# LTR-329ALS-01_StemmaQT.net
KiCad netlist of a schematic drawn in Altium Designer
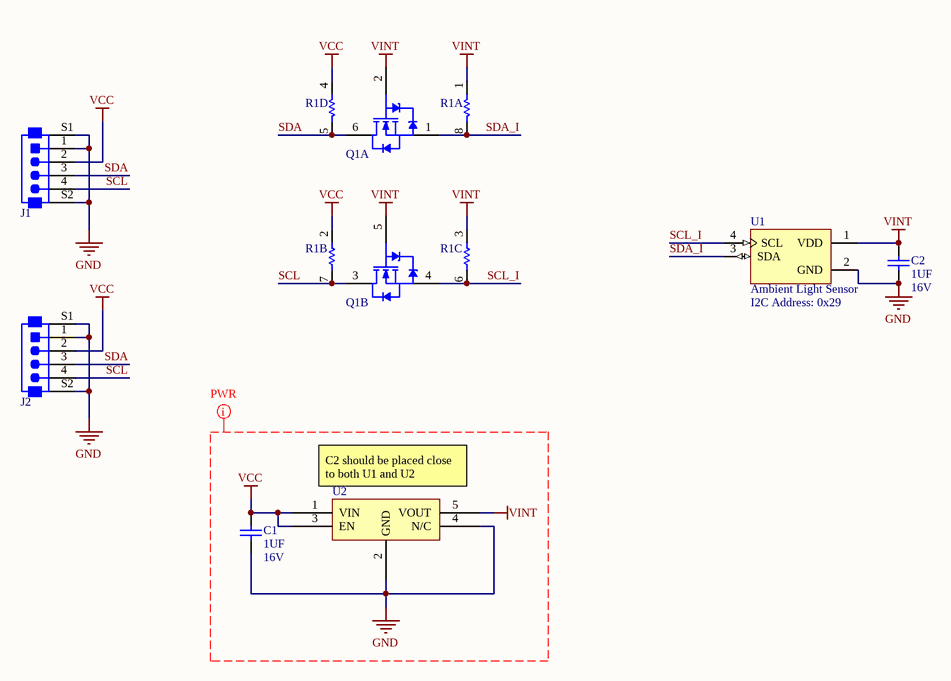
[diagram p0: LTR-329ALS-01 StemmaQT.SchDoc]

(export (version "E")
  (design (tool "Eeschema 10.0.6"))
  (components
    (comp (ref "C1")
      (value "CAP 0603 1UF 16V 10% X7R")
      (footprint "0603_CAP")
      (description "Capacitor Surface Mount 0603 Footprint 1UF 16V 10% Tolerance Ceramic X7R")
      (fields
        (field (name "VAL") "1UF")
        (field (name "VOL") "16V")
        (field (name "MANUFACTURER") "Various")
        (field (name "VOLTAGE") "16V")
      )
      (libsource (lib "Passive Components") (part "cap"))
    )
    (comp (ref "C2")
      (value "CAP 0603 1UF 16V 10% X7R")
      (footprint "0603_CAP")
      (description "Capacitor Surface Mount 0603 Footprint 1UF 16V 10% Tolerance Ceramic X7R")
      (fields
        (field (name "VAL") "1UF")
        (field (name "VOL") "16V")
        (field (name "MANUFACTURER") "Various")
        (field (name "VOLTAGE") "16V")
      )
      (libsource (lib "Passive Components") (part "cap"))
    )
    (comp (ref "J1")
      (value "4 Pin, 1mm")
      (footprint "SM04B-SRSS-TB")
      (description "JST 4-Pin SR Series, SMD (1MM, 4 Pos)")
      (fields (field (name "MANUFACTURER") "J.S.T. Mfg. Co.,Ltd"))
      (libsource (lib "Connectors") (part "Header 1X4 2 SHIELD SIDE"))
    )
    (comp (ref "J2")
      (value "4 Pin, 1mm")
      (footprint "SM04B-SRSS-TB")
      (description "JST 4-Pin SR Series, SMD (1MM, 4 Pos)")
      (fields (field (name "MANUFACTURER") "J.S.T. Mfg. Co.,Ltd"))
      (libsource (lib "Connectors") (part "Header 1X4 2 SHIELD SIDE"))
    )
    (comp (ref "Q1")
      (value "Dual N-Channel MOSFET")
      (footprint "SOT363")
      (description "Dual N-Channel Trench MOSFET, 60 V, 0.32 A SOT-363")
      (fields (field (name "MANUFACTURER") "NXP Semiconductors"))
      (libsource (lib "Discrete Semiconductors") (part "BSS138BKS"))
    )
    (comp (ref "R1")
      (value "10k ohm resistor array")
      (footprint "CAY16-J4")
      (fields (field (name "MANUFACTURER") "Bourns Inc."))
      (libsource (lib "Passive Components") (part "res_pack_4"))
    )
    (comp (ref "U1")
      (value "Ambient Light Sensor")
      (footprint "LTR-329ALS-01-MFG")
      (description "Optical Sensor Ambient  I²C 4-VDFN")
      (fields (field (name "I2C ADDRESS") "0x29") (field (name "MANUFACTURER") "Lite-On Inc."))
      (libsource (lib "Sensors") (part "LTR-329ALS-01"))
    )
    (comp (ref "U2")
      (value "2.5V LDO")
      (footprint "SOT23-5")
      (description "Linear Voltage Regulator IC  1 Output  250mA SOT-23-5")
      (fields (field (name "MANUFACTURER") "Texas Insturments"))
      (libsource (lib "Integrated Circuits") (part "LP5907MFX"))
    )
  )
  (nets
    (net (code "1") (name "/SCL") (class "Default")
      (node (ref "J1") (pin "4") (pinfunction "4_4") (pintype "passive"))
      (node (ref "J2") (pin "4") (pinfunction "4_4") (pintype "passive"))
      (node (ref "Q1") (pin "3") (pinfunction "D2_3") (pintype "passive"))
      (node (ref "R1") (pin "7") (pinfunction "7_7") (pintype "passive"))
    )
    (net (code "2") (name "/SCL_I") (class "Default")
      (node (ref "Q1") (pin "4") (pinfunction "S2_4") (pintype "passive"))
      (node (ref "R1") (pin "6") (pinfunction "6_6") (pintype "passive"))
      (node (ref "U1") (pin "4") (pinfunction "SCL_4") (pintype "input"))
    )
    (net (code "3") (name "/SDA") (class "Default")
      (node (ref "J1") (pin "3") (pinfunction "3_3") (pintype "passive"))
      (node (ref "J2") (pin "3") (pinfunction "3_3") (pintype "passive"))
      (node (ref "Q1") (pin "6") (pinfunction "D1_6") (pintype "passive"))
      (node (ref "R1") (pin "5") (pinfunction "5_5") (pintype "passive"))
    )
    (net (code "4") (name "/SDA_I") (class "Default")
      (node (ref "Q1") (pin "1") (pinfunction "S1_1") (pintype "passive"))
      (node (ref "R1") (pin "8") (pinfunction "8_8") (pintype "passive"))
      (node (ref "U1") (pin "3") (pinfunction "SDA_3") (pintype "bidirectional"))
    )
    (net (code "5") (name "GND") (class "Default")
      (node (ref "C1") (pin "1") (pinfunction "1_1") (pintype "passive"))
      (node (ref "C2") (pin "1") (pinfunction "1_1") (pintype "passive"))
      (node (ref "J1") (pin "1") (pinfunction "1_1") (pintype "passive"))
      (node (ref "J1") (pin "S1") (pinfunction "SHIELD_S1") (pintype "power_in"))
      (node (ref "J1") (pin "S2") (pinfunction "SHIELD_S2") (pintype "power_in"))
      (node (ref "J2") (pin "1") (pinfunction "1_1") (pintype "passive"))
      (node (ref "J2") (pin "S1") (pinfunction "SHIELD_S1") (pintype "power_in"))
      (node (ref "J2") (pin "S2") (pinfunction "SHIELD_S2") (pintype "power_in"))
      (node (ref "U1") (pin "2") (pinfunction "GND_2") (pintype "passive"))
      (node (ref "U2") (pin "2") (pinfunction "GND_2") (pintype "passive"))
      (node (ref "U2") (pin "4") (pinfunction "N/C_4") (pintype "passive"))
    )
    (net (code "6") (name "VCC") (class "Default")
      (node (ref "C1") (pin "2") (pinfunction "2_2") (pintype "passive"))
      (node (ref "J1") (pin "2") (pinfunction "2_2") (pintype "passive"))
      (node (ref "J2") (pin "2") (pinfunction "2_2") (pintype "passive"))
      (node (ref "R1") (pin "2") (pinfunction "2_2") (pintype "passive"))
      (node (ref "R1") (pin "4") (pinfunction "4_4") (pintype "passive"))
      (node (ref "U2") (pin "1") (pinfunction "VIN_1") (pintype "passive"))
      (node (ref "U2") (pin "3") (pinfunction "EN_3") (pintype "passive"))
    )
    (net (code "7") (name "VINT") (class "Default")
      (node (ref "C2") (pin "2") (pinfunction "2_2") (pintype "passive"))
      (node (ref "Q1") (pin "2") (pinfunction "G1_2") (pintype "passive"))
      (node (ref "Q1") (pin "5") (pinfunction "G2_5") (pintype "passive"))
      (node (ref "R1") (pin "1") (pinfunction "1_1") (pintype "passive"))
      (node (ref "R1") (pin "3") (pinfunction "3_3") (pintype "passive"))
      (node (ref "U1") (pin "1") (pinfunction "VDD_1") (pintype "power_in"))
      (node (ref "U2") (pin "5") (pinfunction "VOUT_5") (pintype "passive"))
    )
  )
)
